# h-bridge_driver_general_AB.net
KiCad netlist of a schematic drawn in EAGLE
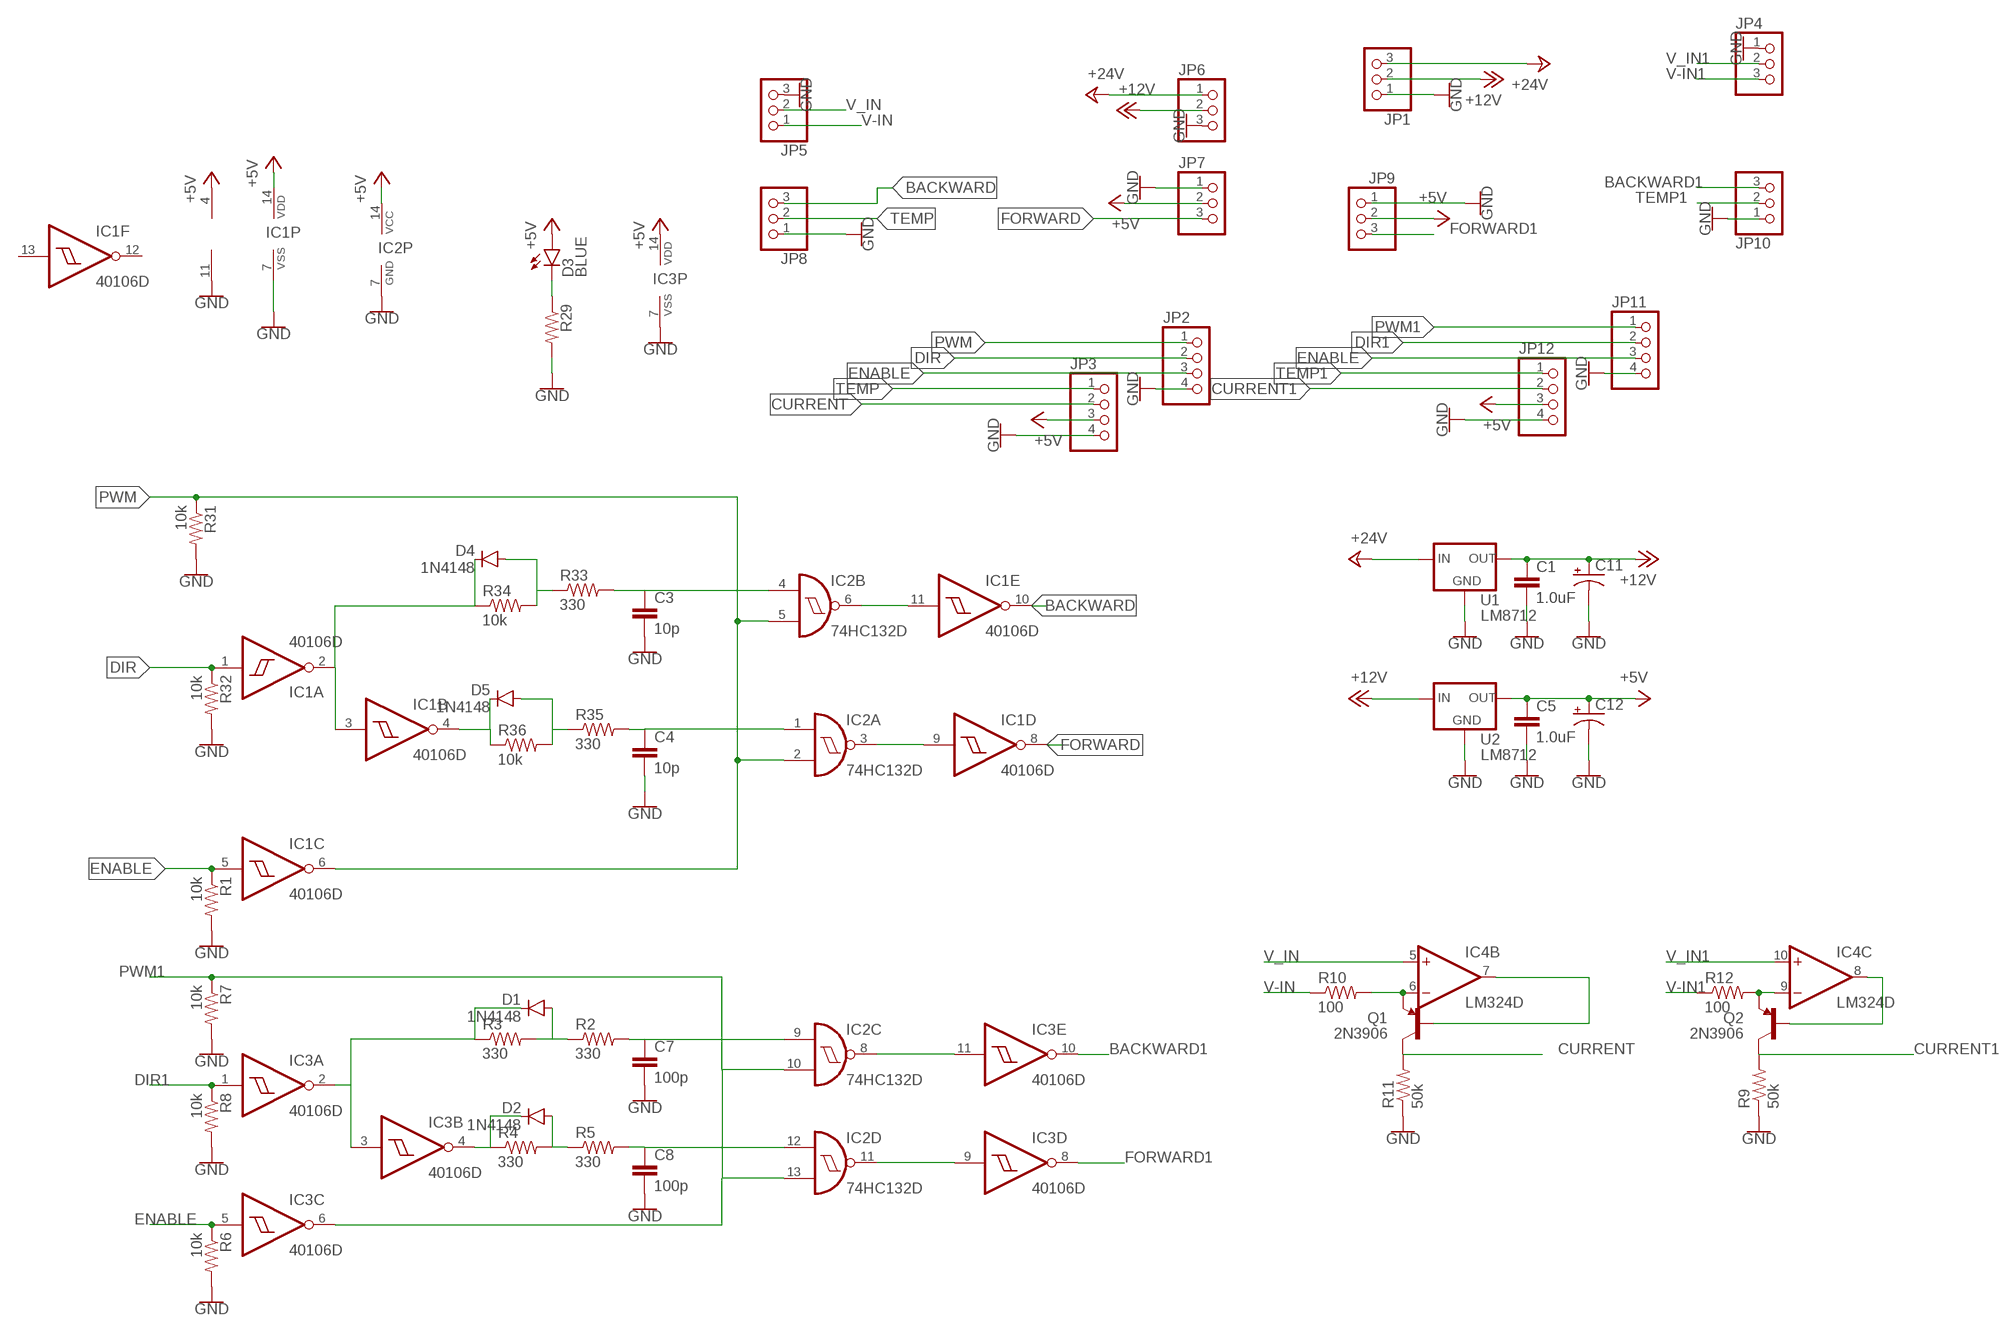
[diagram p0: schematic, sheet 1]

(export (version "E")
  (design (tool "Eeschema 10.0.6"))
  (components
    (comp (ref "C1")
      (value "1.0uF")
      (footprint "eagle-import:1206")
      (libsource (lib "eagle-import") (part "1.0UF50V10%(1206)"))
    )
    (comp (ref "C3")
      (value "10p")
      (footprint "eagle-import:0805-CAP")
      (libsource (lib "eagle-import") (part "1.0UF-25V-+80/-20(0805){dblquote}"))
    )
    (comp (ref "C4")
      (value "10p")
      (footprint "eagle-import:0805-CAP")
      (libsource (lib "eagle-import") (part "1.0UF-25V-+80/-20(0805){dblquote}"))
    )
    (comp (ref "C5")
      (value "1.0uF")
      (footprint "eagle-import:1206")
      (libsource (lib "eagle-import") (part "1.0UF50V10%(1206)"))
    )
    (comp (ref "C7")
      (value "100p")
      (footprint "eagle-import:0805-CAP")
      (libsource (lib "eagle-import") (part "1.0UF-25V-+80/-20(0805){dblquote}"))
    )
    (comp (ref "C8")
      (value "100p")
      (footprint "eagle-import:0805-CAP")
      (libsource (lib "eagle-import") (part "1.0UF-25V-+80/-20(0805){dblquote}"))
    )
    (comp (ref "C11")
      (value "CAP_POLPTH4")
      (footprint "eagle-import:CPOL-RADIAL-1000UF-25V")
      (libsource (lib "eagle-import") (part "CAP_POLPTH4"))
    )
    (comp (ref "C12")
      (value "CAP_POLPTH4")
      (footprint "eagle-import:CPOL-RADIAL-1000UF-25V")
      (libsource (lib "eagle-import") (part "CAP_POLPTH4"))
    )
    (comp (ref "D1")
      (value "1N4148")
      (footprint "eagle-import:SOD-123")
      (libsource (lib "eagle-import") (part "DIODESOD123"))
    )
    (comp (ref "D2")
      (value "1N4148")
      (footprint "eagle-import:SOD-123")
      (libsource (lib "eagle-import") (part "DIODESOD123"))
    )
    (comp (ref "D3")
      (value "BLUE")
      (footprint "eagle-import:LED-1206")
      (libsource (lib "eagle-import") (part "LED-BLUE1206"))
    )
    (comp (ref "D4")
      (value "1N4148")
      (footprint "eagle-import:SOD-123")
      (libsource (lib "eagle-import") (part "DIODESOD123"))
    )
    (comp (ref "D5")
      (value "1N4148")
      (footprint "eagle-import:SOD-123")
      (libsource (lib "eagle-import") (part "DIODESOD123"))
    )
    (comp (ref "IC1")
      (value "40106D")
      (footprint "eagle-import:SO14")
      (libsource (lib "eagle-import") (part "40106D"))
    )
    (comp (ref "IC2")
      (value "74HC132D")
      (footprint "eagle-import:SO14")
      (libsource (lib "eagle-import") (part "74132DHC"))
    )
    (comp (ref "IC3")
      (value "40106D")
      (footprint "eagle-import:SO14")
      (libsource (lib "eagle-import") (part "40106D"))
    )
    (comp (ref "IC4")
      (value "LM324D")
      (footprint "eagle-import:SO14")
      (libsource (lib "eagle-import") (part "LM324D"))
    )
    (comp (ref "JP1")
      (value "PINHD-1X3")
      (footprint "eagle-import:1X03")
      (libsource (lib "eagle-import") (part "PINHD-1X3"))
    )
    (comp (ref "JP2")
      (value "PINHD-1X4")
      (footprint "eagle-import:1X04")
      (libsource (lib "eagle-import") (part "PINHD-1X4"))
    )
    (comp (ref "JP3")
      (value "PINHD-1X4")
      (footprint "eagle-import:1X04")
      (libsource (lib "eagle-import") (part "PINHD-1X4"))
    )
    (comp (ref "JP4")
      (value "PINHD-1X3")
      (footprint "eagle-import:1X03")
      (libsource (lib "eagle-import") (part "PINHD-1X3"))
    )
    (comp (ref "JP5")
      (value "PINHD-1X3")
      (footprint "eagle-import:1X03")
      (libsource (lib "eagle-import") (part "PINHD-1X3"))
    )
    (comp (ref "JP6")
      (value "PINHD-1X3")
      (footprint "eagle-import:1X03")
      (libsource (lib "eagle-import") (part "PINHD-1X3"))
    )
    (comp (ref "JP7")
      (value "PINHD-1X3")
      (footprint "eagle-import:1X03")
      (libsource (lib "eagle-import") (part "PINHD-1X3"))
    )
    (comp (ref "JP8")
      (value "PINHD-1X3")
      (footprint "eagle-import:1X03")
      (libsource (lib "eagle-import") (part "PINHD-1X3"))
    )
    (comp (ref "JP9")
      (value "PINHD-1X3")
      (footprint "eagle-import:1X03")
      (libsource (lib "eagle-import") (part "PINHD-1X3"))
    )
    (comp (ref "JP10")
      (value "PINHD-1X3")
      (footprint "eagle-import:1X03")
      (libsource (lib "eagle-import") (part "PINHD-1X3"))
    )
    (comp (ref "JP11")
      (value "PINHD-1X4")
      (footprint "eagle-import:1X04")
      (libsource (lib "eagle-import") (part "PINHD-1X4"))
    )
    (comp (ref "JP12")
      (value "PINHD-1X4")
      (footprint "eagle-import:1X04")
      (libsource (lib "eagle-import") (part "PINHD-1X4"))
    )
    (comp (ref "Q1")
      (value "2N3906")
      (footprint "eagle-import:SOT23-3")
      (libsource (lib "eagle-import") (part "TRANSISTOR_PNPMMBT4403"))
    )
    (comp (ref "Q2")
      (value "2N3906")
      (footprint "eagle-import:SOT23-3")
      (libsource (lib "eagle-import") (part "TRANSISTOR_PNPMMBT4403"))
    )
    (comp (ref "R1")
      (value "10k")
      (footprint "eagle-import:0805")
      (libsource (lib "eagle-import") (part "0.3OHM-1/8W-1%(0805)"))
    )
    (comp (ref "R2")
      (value "330")
      (footprint "eagle-import:0805")
      (libsource (lib "eagle-import") (part "0.3OHM-1/8W-1%(0805)"))
    )
    (comp (ref "R3")
      (value "330")
      (footprint "eagle-import:0805")
      (libsource (lib "eagle-import") (part "0.3OHM-1/8W-1%(0805)"))
    )
    (comp (ref "R4")
      (value "330")
      (footprint "eagle-import:0805")
      (libsource (lib "eagle-import") (part "0.3OHM-1/8W-1%(0805)"))
    )
    (comp (ref "R5")
      (value "330")
      (footprint "eagle-import:0805")
      (libsource (lib "eagle-import") (part "0.3OHM-1/8W-1%(0805)"))
    )
    (comp (ref "R6")
      (value "10k")
      (footprint "eagle-import:0805")
      (libsource (lib "eagle-import") (part "0.3OHM-1/8W-1%(0805)"))
    )
    (comp (ref "R7")
      (value "10k")
      (footprint "eagle-import:0805")
      (libsource (lib "eagle-import") (part "0.3OHM-1/8W-1%(0805)"))
    )
    (comp (ref "R8")
      (value "10k")
      (footprint "eagle-import:0805")
      (libsource (lib "eagle-import") (part "0.3OHM-1/8W-1%(0805)"))
    )
    (comp (ref "R9")
      (value "50k")
      (footprint "eagle-import:0805")
      (libsource (lib "eagle-import") (part "0.3OHM-1/8W-1%(0805)"))
    )
    (comp (ref "R10")
      (value "100")
      (footprint "eagle-import:0805")
      (libsource (lib "eagle-import") (part "0.3OHM-1/8W-1%(0805)"))
    )
    (comp (ref "R11")
      (value "50k")
      (footprint "eagle-import:0805")
      (libsource (lib "eagle-import") (part "0.3OHM-1/8W-1%(0805)"))
    )
    (comp (ref "R12")
      (value "100")
      (footprint "eagle-import:0805")
      (libsource (lib "eagle-import") (part "0.3OHM-1/8W-1%(0805)"))
    )
    (comp (ref "R29")
      (value "0.3OHM-1/8W-1%(0805)")
      (footprint "eagle-import:0805")
      (libsource (lib "eagle-import") (part "0.3OHM-1/8W-1%(0805)"))
    )
    (comp (ref "R31")
      (value "10k")
      (footprint "eagle-import:0805")
      (libsource (lib "eagle-import") (part "0.3OHM-1/8W-1%(0805)"))
    )
    (comp (ref "R32")
      (value "10k")
      (footprint "eagle-import:0805")
      (libsource (lib "eagle-import") (part "0.3OHM-1/8W-1%(0805)"))
    )
    (comp (ref "R33")
      (value "330")
      (footprint "eagle-import:0805")
      (libsource (lib "eagle-import") (part "0.3OHM-1/8W-1%(0805)"))
    )
    (comp (ref "R34")
      (value "10k")
      (footprint "eagle-import:0805")
      (libsource (lib "eagle-import") (part "0.3OHM-1/8W-1%(0805)"))
    )
    (comp (ref "R35")
      (value "330")
      (footprint "eagle-import:0805")
      (libsource (lib "eagle-import") (part "0.3OHM-1/8W-1%(0805)"))
    )
    (comp (ref "R36")
      (value "10k")
      (footprint "eagle-import:0805")
      (libsource (lib "eagle-import") (part "0.3OHM-1/8W-1%(0805)"))
    )
    (comp (ref "U1")
      (value "LM8712")
      (footprint "eagle-import:78XXL")
      (libsource (lib "eagle-import") (part "V_REG_78XXSIDE"))
    )
    (comp (ref "U2")
      (value "LM8712")
      (footprint "eagle-import:78XXL")
      (libsource (lib "eagle-import") (part "V_REG_78XXSIDE"))
    )
  )
  (nets
    (net (code "1") (name "+5V") (class "Default")
      (node (ref "C12") (pin "+") (pinfunction "+_+") (pintype "passive"))
      (node (ref "C5") (pin "1") (pinfunction "1_1") (pintype "passive"))
      (node (ref "D3") (pin "A") (pinfunction "A_A") (pintype "passive"))
      (node (ref "IC1") (pin "14") (pinfunction "VDD_14") (pintype "power_in"))
      (node (ref "IC2") (pin "14") (pinfunction "VCC_14") (pintype "power_in"))
      (node (ref "IC3") (pin "14") (pinfunction "VDD_14") (pintype "power_in"))
      (node (ref "IC4") (pin "4") (pinfunction "V+_4") (pintype "power_in"))
      (node (ref "JP12") (pin "3") (pinfunction "3_3") (pintype "passive"))
      (node (ref "JP3") (pin "3") (pinfunction "3_3") (pintype "passive"))
      (node (ref "JP7") (pin "2") (pinfunction "2_2") (pintype "passive"))
      (node (ref "JP9") (pin "2") (pinfunction "2_2") (pintype "passive"))
      (node (ref "U2") (pin "OUT") (pinfunction "OUT_OUT") (pintype "passive"))
    )
    (net (code "2") (name "+12V") (class "Default")
      (node (ref "C1") (pin "1") (pinfunction "1_1") (pintype "passive"))
      (node (ref "C11") (pin "+") (pinfunction "+_+") (pintype "passive"))
      (node (ref "JP1") (pin "2") (pinfunction "2_2") (pintype "passive"))
      (node (ref "JP6") (pin "2") (pinfunction "2_2") (pintype "passive"))
      (node (ref "U1") (pin "OUT") (pinfunction "OUT_OUT") (pintype "passive"))
      (node (ref "U2") (pin "IN") (pinfunction "IN_IN") (pintype "input"))
    )
    (net (code "3") (name "+24V") (class "Default")
      (node (ref "JP1") (pin "3") (pinfunction "3_3") (pintype "passive"))
      (node (ref "JP6") (pin "1") (pinfunction "1_1") (pintype "passive"))
      (node (ref "U1") (pin "IN") (pinfunction "IN_IN") (pintype "input"))
    )
    (net (code "4") (name "/BACKWARD1") (class "Default")
      (node (ref "IC3") (pin "10") (pinfunction "O_10") (pintype "output"))
      (node (ref "JP10") (pin "3") (pinfunction "3_3") (pintype "passive"))
    )
    (net (code "5") (name "/FORWARD1") (class "Default")
      (node (ref "IC3") (pin "8") (pinfunction "O_8") (pintype "output"))
      (node (ref "JP9") (pin "3") (pinfunction "3_3") (pintype "passive"))
    )
    (net (code "6") (name "/V-IN") (class "Default")
      (node (ref "JP5") (pin "1") (pinfunction "1_1") (pintype "passive"))
      (node (ref "R10") (pin "1") (pinfunction "1_1") (pintype "passive"))
    )
    (net (code "7") (name "/V-IN1") (class "Default")
      (node (ref "JP4") (pin "3") (pinfunction "3_3") (pintype "passive"))
      (node (ref "R12") (pin "1") (pinfunction "1_1") (pintype "passive"))
    )
    (net (code "8") (name "/V_IN") (class "Default")
      (node (ref "IC4") (pin "5") (pinfunction "+IN_5") (pintype "input"))
      (node (ref "JP5") (pin "2") (pinfunction "2_2") (pintype "passive"))
    )
    (net (code "9") (name "/V_IN1") (class "Default")
      (node (ref "IC4") (pin "10") (pinfunction "+IN_10") (pintype "input"))
      (node (ref "JP4") (pin "2") (pinfunction "2_2") (pintype "passive"))
    )
    (net (code "10") (name "BACKWARD") (class "Default")
      (node (ref "IC1") (pin "10") (pinfunction "O_10") (pintype "output"))
      (node (ref "JP8") (pin "3") (pinfunction "3_3") (pintype "passive"))
    )
    (net (code "11") (name "CURRENT") (class "Default")
      (node (ref "JP3") (pin "2") (pinfunction "2_2") (pintype "passive"))
      (node (ref "Q1") (pin "3") (pinfunction "C_3") (pintype "passive"))
      (node (ref "R11") (pin "2") (pinfunction "2_2") (pintype "passive"))
    )
    (net (code "12") (name "CURRENT1") (class "Default")
      (node (ref "JP12") (pin "2") (pinfunction "2_2") (pintype "passive"))
      (node (ref "Q2") (pin "3") (pinfunction "C_3") (pintype "passive"))
      (node (ref "R9") (pin "2") (pinfunction "2_2") (pintype "passive"))
    )
    (net (code "13") (name "DIR") (class "Default")
      (node (ref "IC1") (pin "1") (pinfunction "I_1") (pintype "input"))
      (node (ref "JP2") (pin "2") (pinfunction "2_2") (pintype "passive"))
      (node (ref "R32") (pin "1") (pinfunction "1_1") (pintype "passive"))
    )
    (net (code "14") (name "DIR1") (class "Default")
      (node (ref "IC3") (pin "1") (pinfunction "I_1") (pintype "input"))
      (node (ref "JP11") (pin "2") (pinfunction "2_2") (pintype "passive"))
      (node (ref "R8") (pin "1") (pinfunction "1_1") (pintype "passive"))
    )
    (net (code "15") (name "ENABLE") (class "Default")
      (node (ref "IC1") (pin "5") (pinfunction "I_5") (pintype "input"))
      (node (ref "IC3") (pin "5") (pinfunction "I_5") (pintype "input"))
      (node (ref "JP11") (pin "3") (pinfunction "3_3") (pintype "passive"))
      (node (ref "JP2") (pin "3") (pinfunction "3_3") (pintype "passive"))
      (node (ref "R1") (pin "1") (pinfunction "1_1") (pintype "passive"))
      (node (ref "R6") (pin "1") (pinfunction "1_1") (pintype "passive"))
    )
    (net (code "16") (name "FORWARD") (class "Default")
      (node (ref "IC1") (pin "8") (pinfunction "O_8") (pintype "output"))
      (node (ref "JP7") (pin "3") (pinfunction "3_3") (pintype "passive"))
    )
    (net (code "17") (name "GND") (class "Default")
      (node (ref "C1") (pin "2") (pinfunction "2_2") (pintype "passive"))
      (node (ref "C11") (pin "-") (pinfunction "-_-") (pintype "passive"))
      (node (ref "C12") (pin "-") (pinfunction "-_-") (pintype "passive"))
      (node (ref "C3") (pin "2") (pinfunction "2_2") (pintype "passive"))
      (node (ref "C4") (pin "2") (pinfunction "2_2") (pintype "passive"))
      (node (ref "C5") (pin "2") (pinfunction "2_2") (pintype "passive"))
      (node (ref "C7") (pin "2") (pinfunction "2_2") (pintype "passive"))
      (node (ref "C8") (pin "2") (pinfunction "2_2") (pintype "passive"))
      (node (ref "IC1") (pin "7") (pinfunction "VSS_7") (pintype "power_in"))
      (node (ref "IC2") (pin "7") (pinfunction "GND_7") (pintype "power_in"))
      (node (ref "IC3") (pin "7") (pinfunction "VSS_7") (pintype "power_in"))
      (node (ref "IC4") (pin "11") (pinfunction "V-_11") (pintype "power_in"))
      (node (ref "JP1") (pin "1") (pinfunction "1_1") (pintype "passive"))
      (node (ref "JP10") (pin "1") (pinfunction "1_1") (pintype "passive"))
      (node (ref "JP11") (pin "4") (pinfunction "4_4") (pintype "passive"))
      (node (ref "JP12") (pin "4") (pinfunction "4_4") (pintype "passive"))
      (node (ref "JP2") (pin "4") (pinfunction "4_4") (pintype "passive"))
      (node (ref "JP3") (pin "4") (pinfunction "4_4") (pintype "passive"))
      (node (ref "JP4") (pin "1") (pinfunction "1_1") (pintype "passive"))
      (node (ref "JP5") (pin "3") (pinfunction "3_3") (pintype "passive"))
      (node (ref "JP6") (pin "3") (pinfunction "3_3") (pintype "passive"))
      (node (ref "JP7") (pin "1") (pinfunction "1_1") (pintype "passive"))
      (node (ref "JP8") (pin "1") (pinfunction "1_1") (pintype "passive"))
      (node (ref "JP9") (pin "1") (pinfunction "1_1") (pintype "passive"))
      (node (ref "R1") (pin "2") (pinfunction "2_2") (pintype "passive"))
      (node (ref "R11") (pin "1") (pinfunction "1_1") (pintype "passive"))
      (node (ref "R29") (pin "2") (pinfunction "2_2") (pintype "passive"))
      (node (ref "R31") (pin "2") (pinfunction "2_2") (pintype "passive"))
      (node (ref "R32") (pin "2") (pinfunction "2_2") (pintype "passive"))
      (node (ref "R6") (pin "2") (pinfunction "2_2") (pintype "passive"))
      (node (ref "R7") (pin "2") (pinfunction "2_2") (pintype "passive"))
      (node (ref "R8") (pin "2") (pinfunction "2_2") (pintype "passive"))
      (node (ref "R9") (pin "1") (pinfunction "1_1") (pintype "passive"))
      (node (ref "U1") (pin "GND") (pinfunction "GND_GND") (pintype "input"))
      (node (ref "U2") (pin "GND") (pinfunction "GND_GND") (pintype "input"))
    )
    (net (code "18") (name "Net-(D1-PadA)") (class "Default")
      (node (ref "D1") (pin "A") (pinfunction "A_A") (pintype "passive"))
      (node (ref "R2") (pin "1") (pinfunction "1_1") (pintype "passive"))
      (node (ref "R3") (pin "2") (pinfunction "2_2") (pintype "passive"))
    )
    (net (code "19") (name "Net-(D2-PadA)") (class "Default")
      (node (ref "D2") (pin "A") (pinfunction "A_A") (pintype "passive"))
      (node (ref "R4") (pin "2") (pinfunction "2_2") (pintype "passive"))
      (node (ref "R5") (pin "1") (pinfunction "1_1") (pintype "passive"))
    )
    (net (code "20") (name "Net-(D3-PadC)") (class "Default")
      (node (ref "D3") (pin "C") (pinfunction "C_C") (pintype "passive"))
      (node (ref "R29") (pin "1") (pinfunction "1_1") (pintype "passive"))
    )
    (net (code "21") (name "Net-(D4-PadA)") (class "Default")
      (node (ref "D4") (pin "A") (pinfunction "A_A") (pintype "passive"))
      (node (ref "R33") (pin "1") (pinfunction "1_1") (pintype "passive"))
      (node (ref "R34") (pin "2") (pinfunction "2_2") (pintype "passive"))
    )
    (net (code "22") (name "Net-(D5-PadA)") (class "Default")
      (node (ref "D5") (pin "A") (pinfunction "A_A") (pintype "passive"))
      (node (ref "R35") (pin "1") (pinfunction "1_1") (pintype "passive"))
      (node (ref "R36") (pin "2") (pinfunction "2_2") (pintype "passive"))
    )
    (net (code "23") (name "Net-(IC1A-O)") (class "Default")
      (node (ref "D4") (pin "C") (pinfunction "C_C") (pintype "passive"))
      (node (ref "IC1") (pin "2") (pinfunction "O_2") (pintype "output"))
      (node (ref "IC1") (pin "3") (pinfunction "I_3") (pintype "input"))
      (node (ref "R34") (pin "1") (pinfunction "1_1") (pintype "passive"))
    )
    (net (code "24") (name "Net-(IC1B-O)") (class "Default")
      (node (ref "D5") (pin "C") (pinfunction "C_C") (pintype "passive"))
      (node (ref "IC1") (pin "4") (pinfunction "O_4") (pintype "output"))
      (node (ref "R36") (pin "1") (pinfunction "1_1") (pintype "passive"))
    )
    (net (code "25") (name "Net-(IC1D-I)") (class "Default")
      (node (ref "IC1") (pin "9") (pinfunction "I_9") (pintype "input"))
      (node (ref "IC2") (pin "3") (pinfunction "O_3") (pintype "output"))
    )
    (net (code "26") (name "Net-(IC1E-I)") (class "Default")
      (node (ref "IC1") (pin "11") (pinfunction "I_11") (pintype "input"))
      (node (ref "IC2") (pin "6") (pinfunction "O_6") (pintype "output"))
    )
    (net (code "27") (name "Net-(IC2A-I0)") (class "Default")
      (node (ref "C4") (pin "1") (pinfunction "1_1") (pintype "passive"))
      (node (ref "IC2") (pin "1") (pinfunction "I0_1") (pintype "input"))
      (node (ref "R35") (pin "2") (pinfunction "2_2") (pintype "passive"))
    )
    (net (code "28") (name "Net-(IC2B-I0)") (class "Default")
      (node (ref "C3") (pin "1") (pinfunction "1_1") (pintype "passive"))
      (node (ref "IC2") (pin "4") (pinfunction "I0_4") (pintype "input"))
      (node (ref "R33") (pin "2") (pinfunction "2_2") (pintype "passive"))
    )
    (net (code "29") (name "Net-(IC2C-I0)") (class "Default")
      (node (ref "C7") (pin "1") (pinfunction "1_1") (pintype "passive"))
      (node (ref "IC2") (pin "9") (pinfunction "I0_9") (pintype "input"))
      (node (ref "R2") (pin "2") (pinfunction "2_2") (pintype "passive"))
    )
    (net (code "30") (name "Net-(IC2C-O)") (class "Default")
      (node (ref "IC2") (pin "8") (pinfunction "O_8") (pintype "output"))
      (node (ref "IC3") (pin "11") (pinfunction "I_11") (pintype "input"))
    )
    (net (code "31") (name "Net-(IC2D-I0)") (class "Default")
      (node (ref "C8") (pin "1") (pinfunction "1_1") (pintype "passive"))
      (node (ref "IC2") (pin "12") (pinfunction "I0_12") (pintype "input"))
      (node (ref "R5") (pin "2") (pinfunction "2_2") (pintype "passive"))
    )
    (net (code "32") (name "Net-(IC2D-O)") (class "Default")
      (node (ref "IC2") (pin "11") (pinfunction "O_11") (pintype "output"))
      (node (ref "IC3") (pin "9") (pinfunction "I_9") (pintype "input"))
    )
    (net (code "33") (name "Net-(IC3A-O)") (class "Default")
      (node (ref "D1") (pin "C") (pinfunction "C_C") (pintype "passive"))
      (node (ref "IC3") (pin "2") (pinfunction "O_2") (pintype "output"))
      (node (ref "IC3") (pin "3") (pinfunction "I_3") (pintype "input"))
      (node (ref "R3") (pin "1") (pinfunction "1_1") (pintype "passive"))
    )
    (net (code "34") (name "Net-(IC3B-O)") (class "Default")
      (node (ref "D2") (pin "C") (pinfunction "C_C") (pintype "passive"))
      (node (ref "IC3") (pin "4") (pinfunction "O_4") (pintype "output"))
      (node (ref "R4") (pin "1") (pinfunction "1_1") (pintype "passive"))
    )
    (net (code "35") (name "Net-(IC4B--IN)") (class "Default")
      (node (ref "IC4") (pin "6") (pinfunction "-IN_6") (pintype "input"))
      (node (ref "Q1") (pin "2") (pinfunction "E_2") (pintype "passive"))
      (node (ref "R10") (pin "2") (pinfunction "2_2") (pintype "passive"))
    )
    (net (code "36") (name "Net-(IC4B-OUT)") (class "Default")
      (node (ref "IC4") (pin "7") (pinfunction "OUT_7") (pintype "output"))
      (node (ref "Q1") (pin "1") (pinfunction "B_1") (pintype "passive"))
    )
    (net (code "37") (name "Net-(IC4C--IN)") (class "Default")
      (node (ref "IC4") (pin "9") (pinfunction "-IN_9") (pintype "input"))
      (node (ref "Q2") (pin "2") (pinfunction "E_2") (pintype "passive"))
      (node (ref "R12") (pin "2") (pinfunction "2_2") (pintype "passive"))
    )
    (net (code "38") (name "Net-(IC4C-OUT)") (class "Default")
      (node (ref "IC4") (pin "8") (pinfunction "OUT_8") (pintype "output"))
      (node (ref "Q2") (pin "1") (pinfunction "B_1") (pintype "passive"))
    )
    (net (code "39") (name "PWM") (class "Default")
      (node (ref "IC1") (pin "6") (pinfunction "O_6") (pintype "output"))
      (node (ref "IC2") (pin "2") (pinfunction "I1_2") (pintype "input"))
      (node (ref "IC2") (pin "5") (pinfunction "I1_5") (pintype "input"))
      (node (ref "JP2") (pin "1") (pinfunction "1_1") (pintype "passive"))
      (node (ref "R31") (pin "1") (pinfunction "1_1") (pintype "passive"))
    )
    (net (code "40") (name "PWM1") (class "Default")
      (node (ref "IC2") (pin "10") (pinfunction "I1_10") (pintype "input"))
      (node (ref "IC2") (pin "13") (pinfunction "I1_13") (pintype "input"))
      (node (ref "IC3") (pin "6") (pinfunction "O_6") (pintype "output"))
      (node (ref "JP11") (pin "1") (pinfunction "1_1") (pintype "passive"))
      (node (ref "R7") (pin "1") (pinfunction "1_1") (pintype "passive"))
    )
    (net (code "41") (name "TEMP") (class "Default")
      (node (ref "JP3") (pin "1") (pinfunction "1_1") (pintype "passive"))
      (node (ref "JP8") (pin "2") (pinfunction "2_2") (pintype "passive"))
    )
    (net (code "42") (name "TEMP1") (class "Default")
      (node (ref "JP10") (pin "2") (pinfunction "2_2") (pintype "passive"))
      (node (ref "JP12") (pin "1") (pinfunction "1_1") (pintype "passive"))
    )
    (net (code "43") (name "unconnected-(IC1F-I-Pad13)") (class "Default")
      (node (ref "IC1") (pin "13") (pinfunction "I_13") (pintype "input"))
    )
    (net (code "44") (name "unconnected-(IC1F-O-Pad12)") (class "Default")
      (node (ref "IC1") (pin "12") (pinfunction "O_12") (pintype "output"))
    )
  )
)
